# BSPD-rev2.net
KiCad netlist of a schematic drawn in Altium Designer
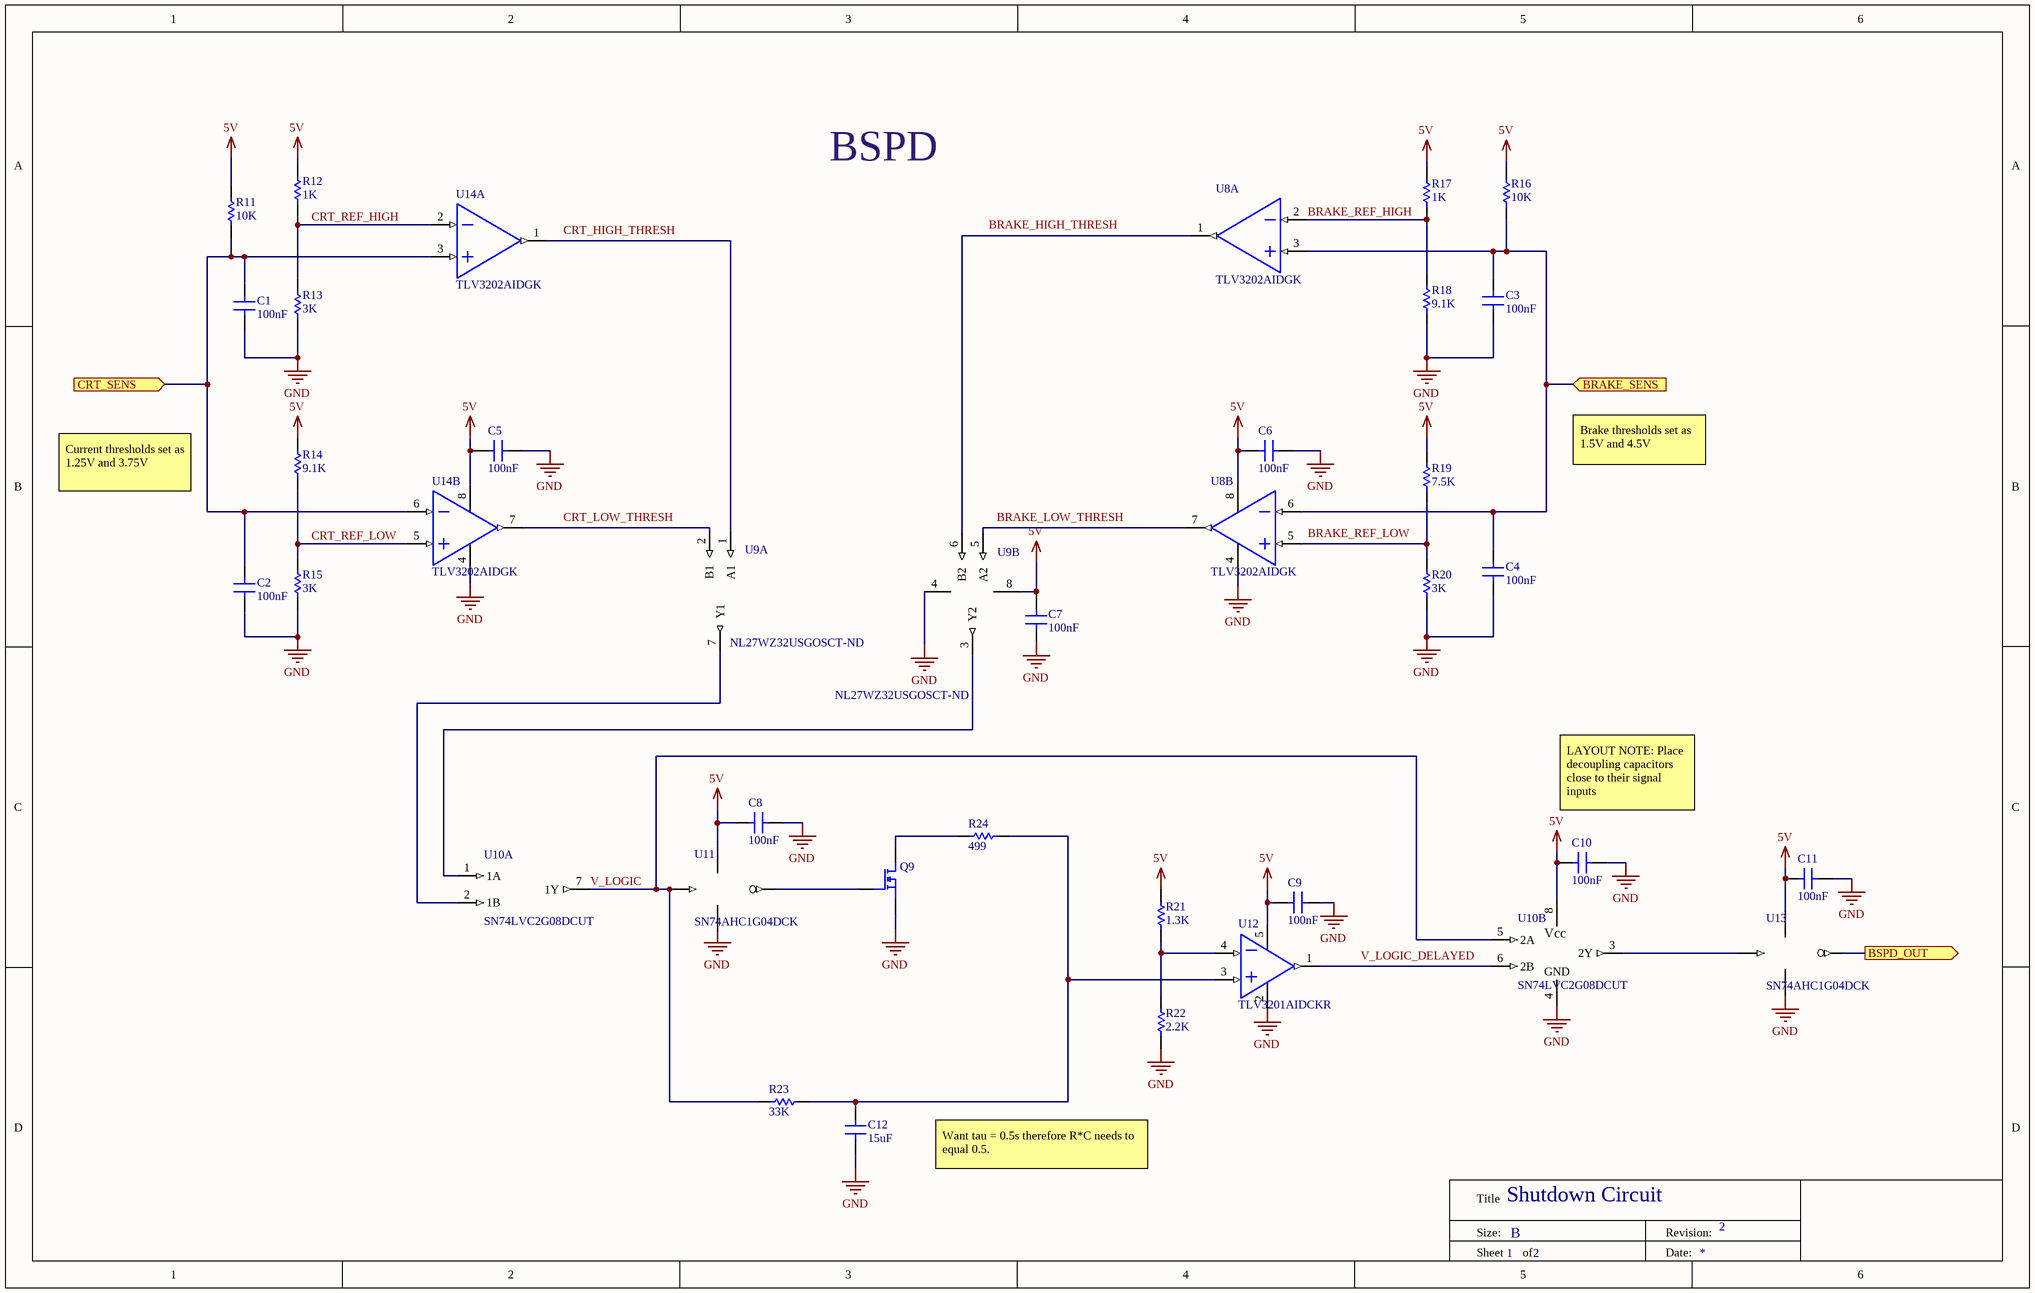
[diagram p0: BSPD-rev2.SchDoc]

(export (version "E")
  (design (tool "Eeschema 10.0.6"))
  (components
    (comp (ref "C1")
      (value "100nF")
      (footprint "CAP-0603")
      (description "CAP CER 0.1UF 50V X7R 0603")
      (fields
        (field (name "MANUFACTURER") "Samsung")
        (field (name "MANUFACTURER PART NUMBER") "CL21A106KPFNNNG")
      )
      (libsource (lib "BSPD") (part "CL10B104KB8NNNL"))
    )
    (comp (ref "C2")
      (value "100nF")
      (footprint "CAP-0603")
      (description "CAP CER 0.1UF 50V X7R 0603")
      (fields
        (field (name "MANUFACTURER") "Samsung")
        (field (name "MANUFACTURER PART NUMBER") "CL21A106KPFNNNG")
      )
      (libsource (lib "BSPD") (part "CL10B104KB8NNNL"))
    )
    (comp (ref "C3")
      (value "100nF")
      (footprint "CAP-0603")
      (description "CAP CER 0.1UF 50V X7R 0603")
      (fields
        (field (name "MANUFACTURER") "Samsung")
        (field (name "MANUFACTURER PART NUMBER") "CL21A106KPFNNNG")
      )
      (libsource (lib "BSPD") (part "CL10B104KB8NNNL"))
    )
    (comp (ref "C4")
      (value "100nF")
      (footprint "CAP-0603")
      (description "CAP CER 0.1UF 50V X7R 0603")
      (fields
        (field (name "MANUFACTURER") "Samsung")
        (field (name "MANUFACTURER PART NUMBER") "CL21A106KPFNNNG")
      )
      (libsource (lib "BSPD") (part "CL10B104KB8NNNL"))
    )
    (comp (ref "C5")
      (value "100nF")
      (footprint "CAP-0603")
      (description "CAP CER 0.1UF 50V X7R 0603")
      (fields
        (field (name "MANUFACTURER") "Samsung")
        (field (name "MANUFACTURER PART NUMBER") "CL21A106KPFNNNG")
      )
      (libsource (lib "BSPD") (part "CL10B104KB8NNNL"))
    )
    (comp (ref "C6")
      (value "100nF")
      (footprint "CAP-0603")
      (description "CAP CER 0.1UF 50V X7R 0603")
      (fields
        (field (name "MANUFACTURER") "Samsung")
        (field (name "MANUFACTURER PART NUMBER") "CL21A106KPFNNNG")
      )
      (libsource (lib "BSPD") (part "CL10B104KB8NNNL"))
    )
    (comp (ref "C7")
      (value "100nF")
      (footprint "CAP-0603")
      (description "CAP CER 0.1UF 50V X7R 0603")
      (fields
        (field (name "MANUFACTURER") "Samsung")
        (field (name "MANUFACTURER PART NUMBER") "CL21A106KPFNNNG")
      )
      (libsource (lib "BSPD") (part "CL10B104KB8NNNL"))
    )
    (comp (ref "C8")
      (value "100nF")
      (footprint "CAP-0603")
      (description "CAP CER 0.1UF 50V X7R 0603")
      (fields
        (field (name "MANUFACTURER") "Samsung")
        (field (name "MANUFACTURER PART NUMBER") "CL21A106KPFNNNG")
      )
      (libsource (lib "BSPD") (part "CL10B104KB8NNNL"))
    )
    (comp (ref "C9")
      (value "100nF")
      (footprint "CAP-0603")
      (description "CAP CER 0.1UF 50V X7R 0603")
      (fields
        (field (name "MANUFACTURER") "Samsung")
        (field (name "MANUFACTURER PART NUMBER") "CL21A106KPFNNNG")
      )
      (libsource (lib "BSPD") (part "CL10B104KB8NNNL"))
    )
    (comp (ref "C10")
      (value "100nF")
      (footprint "CAP-0603")
      (description "CAP CER 0.1UF 50V X7R 0603")
      (fields
        (field (name "MANUFACTURER") "Samsung")
        (field (name "MANUFACTURER PART NUMBER") "CL21A106KPFNNNG")
      )
      (libsource (lib "BSPD") (part "CL10B104KB8NNNL"))
    )
    (comp (ref "C11")
      (value "100nF")
      (footprint "CAP-0603")
      (description "CAP CER 0.1UF 50V X7R 0603")
      (fields
        (field (name "MANUFACTURER") "Samsung")
        (field (name "MANUFACTURER PART NUMBER") "CL21A106KPFNNNG")
      )
      (libsource (lib "BSPD") (part "CL10B104KB8NNNL"))
    )
    (comp (ref "C12")
      (value "15uF")
      (footprint "CAP-0603")
      (description "CAP CER 15UF 6.3V X5R 0603")
      (libsource (lib "BSPD") (part "C1608X5R0J156M080AC"))
    )
    (comp (ref "Q9")
      (value "BSS138LT3G")
      (footprint "SOT-23-3")
      (description "MOSFET N-CH 50V 200MA SOT-23")
      (fields (field (name "MANUFACTURER") "ON Semiconductor"))
      (libsource (lib "BSPD") (part "BSS138LT3G"))
    )
    (comp (ref "R11")
      (value "10K")
      (footprint "RES-0603")
      (description "RES SMD 10K OHM 1% 1/10W 0603")
      (fields
        (field (name "MANUFACTURER") "Vishay")
        (field (name "MANUFACTURER PART NUMBER") "CRCW060310K0FKEA")
      )
      (libsource (lib "SDC") (part "CRCW060310K0FKEA"))
    )
    (comp (ref "R12")
      (value "1K")
      (footprint "RES-0603")
      (description "RES SMD 1K OHM 1% 1/10W 0603")
      (fields
        (field (name "MANUFACTURER") "Vishay Dale")
        (field (name "MANUFACTURER PART NUMBER") "CRCW06031K00FKEA")
      )
      (libsource (lib "SDC") (part "CRCW06031K00FKEA"))
    )
    (comp (ref "R13")
      (value "3K")
      (footprint "RES-0603")
      (description "RES 3K OHM 5% 1/10W 0603")
      (libsource (lib "BSPD") (part "RMCF0603JT3K00"))
    )
    (comp (ref "R14")
      (value "9.1K")
      (footprint "RES-0603")
      (description "RES 9.1K OHM 1% 1/10W 0603")
      (libsource (lib "BSPD") (part "RMCF0603FT9K10"))
    )
    (comp (ref "R15")
      (value "3K")
      (footprint "RES-0603")
      (description "RES 3K OHM 5% 1/10W 0603")
      (libsource (lib "BSPD") (part "RMCF0603JT3K00"))
    )
    (comp (ref "R16")
      (value "10K")
      (footprint "RES-0603")
      (description "RES SMD 10K OHM 1% 1/10W 0603")
      (fields
        (field (name "MANUFACTURER") "Vishay")
        (field (name "MANUFACTURER PART NUMBER") "CRCW060310K0FKEA")
      )
      (libsource (lib "SDC") (part "CRCW060310K0FKEA"))
    )
    (comp (ref "R17")
      (value "1K")
      (footprint "RES-0603")
      (description "RES SMD 1K OHM 1% 1/10W 0603")
      (fields
        (field (name "MANUFACTURER") "Vishay Dale")
        (field (name "MANUFACTURER PART NUMBER") "CRCW06031K00FKEA")
      )
      (libsource (lib "SDC") (part "CRCW06031K00FKEA"))
    )
    (comp (ref "R18")
      (value "9.1K")
      (footprint "RES-0603")
      (description "RES 9.1K OHM 1% 1/10W 0603")
      (libsource (lib "BSPD") (part "RMCF0603FT9K10"))
    )
    (comp (ref "R19")
      (value "7.5K")
      (footprint "RES-0603")
      (description "RES 7.5K OHM 1% 1/8W 0603")
      (libsource (lib "BSPD") (part "RNCP0603FTD7K50"))
    )
    (comp (ref "R20")
      (value "3K")
      (footprint "RES-0603")
      (description "RES 3K OHM 5% 1/10W 0603")
      (libsource (lib "BSPD") (part "RMCF0603JT3K00"))
    )
    (comp (ref "R21")
      (value "1.3K")
      (footprint "RES-0603")
      (description "RES SMD 1.3K OHM 1% 1/8W 0603")
      (libsource (lib "BSPD") (part "MCT06030C1301FP500"))
    )
    (comp (ref "R22")
      (value "2.2K")
      (footprint "RES-0603")
      (description "RES SMD 2.2K OHM 1% 1/10W 0603")
      (libsource (lib "BSPD") (part "RC0603FR-072K2L"))
    )
    (comp (ref "R23")
      (value "33K")
      (footprint "RES-0603")
      (description "RES SMD 33K OHM 1% 1/10W 0603")
      (libsource (lib "BSPD") (part "RC0603FR-0733KL"))
    )
    (comp (ref "R24")
      (value "499")
      (footprint "RES-0603")
      (description "RES SMD 499 OHM 0.1% 1/10W 0603")
      (libsource (lib "BSPD") (part "ERA-3AEB4990V"))
    )
    (comp (ref "U8")
      (value "TLV3202AIDGK")
      (footprint "TLV3202AIDGK")
      (description "IC COMPAR PWR RRI DL PP 8VSSOP")
      (fields (field (name "MANUFACTURER") "Texas Instruments"))
      (libsource (lib "BSPD") (part "TLV3202AIDGK"))
    )
    (comp (ref "U9")
      (value "NL27WZ32USGOSCT-ND")
      (footprint "TSSOP50P310X90-8N")
      (description "IC GATE OR 2CH 2-INP US8")
      (fields
        (field (name "MANUFACTURER") "ON Semiconductor")
        (field (name "MANUFACTURER PART NUMBER") "NL27WZ32USG")
      )
      (libsource (lib "BSPD") (part "NL27WZ32USGOSCT-ND"))
    )
    (comp (ref "U10")
      (value "SN74LVC2G08DCUT")
      (footprint "SN74LVC2G08DCU")
      (description "Dual 2-Input Positive-AND Gate")
      (fields (field (name "MANUFACTURER") "Texas Instruments"))
      (libsource (lib "BSPD") (part "SN74LVC2G08DCUT"))
    )
    (comp (ref "U11")
      (value "SN74AHC1G04DCK")
      (footprint "SN74AHC1G04DCK")
      (description "The SN74AHC1G04 contains one inverter gate. The\r\ndevice performs the Boolean function Y = A bar.")
      (fields
        (field (name "MANUFACTURER") "Texas Instruments")
        (field (name "MANUFACTURER PART NUMBER") "SN74AHC1G04DCKR")
      )
      (libsource (lib "BSPD") (part "SN74AHC1G04DCK"))
    )
    (comp (ref "U12")
      (value "TLV3201AIDCKR")
      (footprint "TLV3201AIDCK")
      (description "Comparator Single R-R I/P 5.5V 5-Pin SC-70 T/R")
      (fields (field (name "MANUFACTURER") "Texas Instruments"))
      (libsource (lib "BSPD") (part "TLV3201AIDCKR"))
    )
    (comp (ref "U13")
      (value "SN74AHC1G04DCK")
      (footprint "SN74AHC1G04DCK")
      (description "The SN74AHC1G04 contains one inverter gate. The\r\ndevice performs the Boolean function Y = A bar.")
      (fields
        (field (name "MANUFACTURER") "Texas Instruments")
        (field (name "MANUFACTURER PART NUMBER") "SN74AHC1G04DCKR")
      )
      (libsource (lib "BSPD") (part "SN74AHC1G04DCK"))
    )
    (comp (ref "U14")
      (value "TLV3202AIDGK")
      (footprint "TLV3202AIDGK")
      (description "IC COMPAR PWR RRI DL PP 8VSSOP")
      (fields (field (name "MANUFACTURER") "Texas Instruments"))
      (libsource (lib "BSPD") (part "TLV3202AIDGK"))
    )
  )
  (nets
    (net (code "4") (name "/BRAKE_REF_HIGH") (class "Default")
      (node (ref "R17") (pin "1") (pinfunction "1_1") (pintype "passive"))
      (node (ref "R18") (pin "2") (pinfunction "2_2") (pintype "passive"))
      (node (ref "U8") (pin "2") (pinfunction "1IN-_2") (pintype "input"))
    )
    (net (code "6") (name "/BRAKE_SENS") (class "Default")
      (node (ref "C3") (pin "2") (pinfunction "2_2") (pintype "passive"))
      (node (ref "C4") (pin "2") (pinfunction "2_2") (pintype "passive"))
      (node (ref "R16") (pin "1") (pinfunction "1_1") (pintype "passive"))
      (node (ref "U8") (pin "3") (pinfunction "1IN+_3") (pintype "input"))
      (node (ref "U8") (pin "6") (pinfunction "2IN-_6") (pintype "input"))
    )
    (net (code "7") (name "/BSPD_OUT") (class "Default")
      (node (ref "U13") (pin "4") (pinfunction "Y_4") (pintype "output"))
    )
    (net (code "10") (name "/CRT_REF_HIGH") (class "Default")
      (node (ref "R12") (pin "1") (pinfunction "1_1") (pintype "passive"))
      (node (ref "R13") (pin "2") (pinfunction "2_2") (pintype "passive"))
      (node (ref "U14") (pin "2") (pinfunction "1IN-_2") (pintype "input"))
    )
    (net (code "11") (name "/CRT_REF_LOW") (class "Default")
      (node (ref "R14") (pin "1") (pinfunction "1_1") (pintype "passive"))
      (node (ref "R15") (pin "2") (pinfunction "2_2") (pintype "passive"))
      (node (ref "U14") (pin "5") (pinfunction "2IN+_5") (pintype "input"))
    )
    (net (code "12") (name "/CRT_SENS") (class "Default")
      (node (ref "C1") (pin "2") (pinfunction "2_2") (pintype "passive"))
      (node (ref "C2") (pin "2") (pinfunction "2_2") (pintype "passive"))
      (node (ref "R11") (pin "1") (pinfunction "1_1") (pintype "passive"))
      (node (ref "U14") (pin "3") (pinfunction "1IN+_3") (pintype "input"))
      (node (ref "U14") (pin "6") (pinfunction "2IN-_6") (pintype "input"))
    )
    (net (code "13") (name "/V_LOGIC") (class "Default")
      (node (ref "R23") (pin "1") (pinfunction "1_1") (pintype "passive"))
      (node (ref "U10") (pin "5") (pinfunction "2A_5") (pintype "input"))
      (node (ref "U10") (pin "7") (pinfunction "1Y_7") (pintype "output"))
      (node (ref "U11") (pin "2") (pinfunction "A_2") (pintype "input"))
    )
    (net (code "15") (name "5V") (class "Default")
      (node (ref "C10") (pin "2") (pinfunction "2_2") (pintype "passive"))
      (node (ref "C11") (pin "2") (pinfunction "2_2") (pintype "passive"))
      (node (ref "C5") (pin "2") (pinfunction "2_2") (pintype "passive"))
      (node (ref "C6") (pin "2") (pinfunction "2_2") (pintype "passive"))
      (node (ref "C7") (pin "1") (pinfunction "1_1") (pintype "passive"))
      (node (ref "C8") (pin "2") (pinfunction "2_2") (pintype "passive"))
      (node (ref "C9") (pin "1") (pinfunction "1_1") (pintype "passive"))
      (node (ref "R11") (pin "2") (pinfunction "2_2") (pintype "passive"))
      (node (ref "R12") (pin "2") (pinfunction "2_2") (pintype "passive"))
      (node (ref "R14") (pin "2") (pinfunction "2_2") (pintype "passive"))
      (node (ref "R16") (pin "2") (pinfunction "2_2") (pintype "passive"))
      (node (ref "R17") (pin "2") (pinfunction "2_2") (pintype "passive"))
      (node (ref "R19") (pin "2") (pinfunction "2_2") (pintype "passive"))
      (node (ref "R21") (pin "2") (pinfunction "2_2") (pintype "passive"))
      (node (ref "U10") (pin "8") (pinfunction "VCC_8") (pintype "power_in"))
      (node (ref "U11") (pin "5") (pinfunction "VCC_5") (pintype "power_in"))
      (node (ref "U12") (pin "5") (pinfunction "VCC_5") (pintype "power_in"))
      (node (ref "U13") (pin "5") (pinfunction "VCC_5") (pintype "power_in"))
      (node (ref "U14") (pin "8") (pinfunction "VCC_8") (pintype "power_in"))
      (node (ref "U8") (pin "8") (pinfunction "VCC_8") (pintype "power_in"))
      (node (ref "U9") (pin "8") (pinfunction "VCC_8") (pintype "power_in"))
    )
    (net (code "16") (name "GND") (class "Default")
      (node (ref "C1") (pin "1") (pinfunction "1_1") (pintype "passive"))
      (node (ref "C10") (pin "1") (pinfunction "1_1") (pintype "passive"))
      (node (ref "C11") (pin "1") (pinfunction "1_1") (pintype "passive"))
      (node (ref "C12") (pin "1") (pinfunction "1_1") (pintype "passive"))
      (node (ref "C2") (pin "1") (pinfunction "1_1") (pintype "passive"))
      (node (ref "C3") (pin "1") (pinfunction "1_1") (pintype "passive"))
      (node (ref "C4") (pin "1") (pinfunction "1_1") (pintype "passive"))
      (node (ref "C5") (pin "1") (pinfunction "1_1") (pintype "passive"))
      (node (ref "C6") (pin "1") (pinfunction "1_1") (pintype "passive"))
      (node (ref "C7") (pin "2") (pinfunction "2_2") (pintype "passive"))
      (node (ref "C8") (pin "1") (pinfunction "1_1") (pintype "passive"))
      (node (ref "C9") (pin "2") (pinfunction "2_2") (pintype "passive"))
      (node (ref "Q9") (pin "2") (pinfunction "2_2") (pintype "passive"))
      (node (ref "R13") (pin "1") (pinfunction "1_1") (pintype "passive"))
      (node (ref "R15") (pin "1") (pinfunction "1_1") (pintype "passive"))
      (node (ref "R18") (pin "1") (pinfunction "1_1") (pintype "passive"))
      (node (ref "R20") (pin "1") (pinfunction "1_1") (pintype "passive"))
      (node (ref "R22") (pin "1") (pinfunction "1_1") (pintype "passive"))
      (node (ref "U10") (pin "4") (pinfunction "GND_4") (pintype "power_in"))
      (node (ref "U12") (pin "2") (pinfunction "GND_2") (pintype "power_in"))
      (node (ref "U13") (pin "3") (pinfunction "GND_3") (pintype "power_in"))
      (node (ref "U14") (pin "4") (pinfunction "GND_4") (pintype "power_in"))
      (node (ref "U8") (pin "4") (pinfunction "GND_4") (pintype "power_in"))
      (node (ref "U9") (pin "4") (pinfunction "GND_4") (pintype "power_in"))
    )
    (net (code "17") (name "Net-(Q9-Pad3)") (class "Default")
      (node (ref "Q9") (pin "3") (pinfunction "3_3") (pintype "passive"))
      (node (ref "R24") (pin "1") (pinfunction "1_1") (pintype "passive"))
    )
    (net (code "18") (name "Net-(U8A-1OUT)") (class "Default")
      (node (ref "U8") (pin "1") (pinfunction "1OUT_1") (pintype "output"))
      (node (ref "U9") (pin "6") (pinfunction "B2_6") (pintype "input"))
    )
    (net (code "19") (name "Net-(U8B-2IN+)") (class "Default")
      (node (ref "R19") (pin "1") (pinfunction "1_1") (pintype "passive"))
      (node (ref "R20") (pin "2") (pinfunction "2_2") (pintype "passive"))
      (node (ref "U8") (pin "5") (pinfunction "2IN+_5") (pintype "input"))
    )
    (net (code "20") (name "Net-(U8B-2OUT)") (class "Default")
      (node (ref "U8") (pin "7") (pinfunction "2OUT_7") (pintype "output"))
      (node (ref "U9") (pin "5") (pinfunction "A2_5") (pintype "input"))
    )
    (net (code "21") (name "Net-(U10A-1A)") (class "Default")
      (node (ref "U10") (pin "1") (pinfunction "1A_1") (pintype "input"))
      (node (ref "U9") (pin "3") (pinfunction "Y2_3") (pintype "output"))
    )
    (net (code "22") (name "Net-(U10A-1B)") (class "Default")
      (node (ref "U10") (pin "2") (pinfunction "1B_2") (pintype "input"))
      (node (ref "U9") (pin "7") (pinfunction "Y1_7") (pintype "output"))
    )
    (net (code "23") (name "Net-(U10B-2B)") (class "Default")
      (node (ref "U10") (pin "6") (pinfunction "2B_6") (pintype "input"))
      (node (ref "U12") (pin "1") (pinfunction "1OUT_1") (pintype "output"))
    )
    (net (code "24") (name "Net-(U10B-2Y)") (class "Default")
      (node (ref "U10") (pin "3") (pinfunction "2Y_3") (pintype "output"))
      (node (ref "U13") (pin "2") (pinfunction "A_2") (pintype "input"))
    )
    (net (code "25") (name "Net-(U11-Y)") (class "Default")
      (node (ref "Q9") (pin "1") (pinfunction "1_1") (pintype "passive"))
      (node (ref "U11") (pin "4") (pinfunction "Y_4") (pintype "output"))
    )
    (net (code "26") (name "Net-(U12-1IN+)") (class "Default")
      (node (ref "C12") (pin "2") (pinfunction "2_2") (pintype "passive"))
      (node (ref "R23") (pin "2") (pinfunction "2_2") (pintype "passive"))
      (node (ref "R24") (pin "2") (pinfunction "2_2") (pintype "passive"))
      (node (ref "U12") (pin "3") (pinfunction "1IN+_3") (pintype "input"))
    )
    (net (code "27") (name "Net-(U12-1IN-)") (class "Default")
      (node (ref "R21") (pin "1") (pinfunction "1_1") (pintype "passive"))
      (node (ref "R22") (pin "2") (pinfunction "2_2") (pintype "passive"))
      (node (ref "U12") (pin "4") (pinfunction "1IN-_4") (pintype "input"))
    )
    (net (code "28") (name "Net-(U14A-1OUT)") (class "Default")
      (node (ref "U14") (pin "1") (pinfunction "1OUT_1") (pintype "output"))
      (node (ref "U9") (pin "1") (pinfunction "A1_1") (pintype "input"))
    )
    (net (code "29") (name "Net-(U14B-2OUT)") (class "Default")
      (node (ref "U14") (pin "7") (pinfunction "2OUT_7") (pintype "output"))
      (node (ref "U9") (pin "2") (pinfunction "B1_2") (pintype "input"))
    )
    (net (code "30") (name "unconnected-(U11-GND-Pad3)") (class "Default")
      (node (ref "U11") (pin "3") (pinfunction "GND_3") (pintype "power_in"))
    )
  )
)
